# Team_Upsilon_Prj2_display_sch.net
KiCad netlist of a schematic drawn in Altium Designer
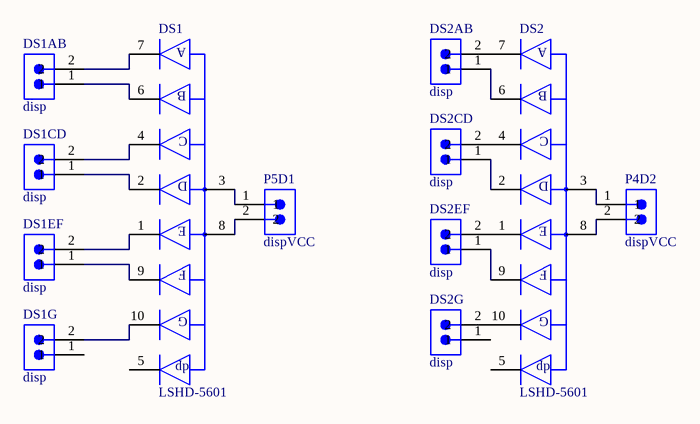
[diagram p0: Team_Upsilon_Prj2_display_sch.SchDoc]

(export (version "E")
  (design (tool "Eeschema 10.0.6"))
  (components
    (comp (ref "DS1")
      (value "LSHD-5601")
      (footprint "FP-LSHD-5601-MFG")
      (description "LED 7-SEG .56\" GREEN 565NM CA")
      (fields
        (field (name "MANUFACTURER") "Lite-On")
        (field (name "OCTOPART") "https://octopart.com/lshd-5601-lite-on-548440")
      )
      (libsource (lib "Altium Content Vault") (part "5a7bf9c30cf36056a9f9d601f88cd94"))
    )
    (comp (ref "DS1AB")
      (value "disp")
      (footprint "61300211121")
      (libsource (lib "Altium Content Vault") (part "Header_Male_1R_02P"))
    )
    (comp (ref "DS1CD")
      (value "disp")
      (footprint "61300211121")
      (libsource (lib "Altium Content Vault") (part "Header_Male_1R_02P"))
    )
    (comp (ref "DS1EF")
      (value "disp")
      (footprint "61300211121")
      (libsource (lib "Altium Content Vault") (part "Header_Male_1R_02P"))
    )
    (comp (ref "DS1G")
      (value "disp")
      (footprint "61300211121")
      (libsource (lib "Altium Content Vault") (part "Header_Male_1R_02P"))
    )
    (comp (ref "DS2")
      (value "LSHD-5601")
      (footprint "FP-LSHD-5601-MFG")
      (description "LED 7-SEG .56\" GREEN 565NM CA")
      (fields
        (field (name "MANUFACTURER") "Lite-On")
        (field (name "OCTOPART") "https://octopart.com/lshd-5601-lite-on-548440")
      )
      (libsource (lib "Altium Content Vault") (part "5a7bf9c30cf36056a9f9d601f88cd94"))
    )
    (comp (ref "DS2AB")
      (value "disp")
      (footprint "61300211121")
      (libsource (lib "Altium Content Vault") (part "Header_Male_1R_02P"))
    )
    (comp (ref "DS2CD")
      (value "disp")
      (footprint "61300211121")
      (libsource (lib "Altium Content Vault") (part "Header_Male_1R_02P"))
    )
    (comp (ref "DS2EF")
      (value "disp")
      (footprint "61300211121")
      (libsource (lib "Altium Content Vault") (part "Header_Male_1R_02P"))
    )
    (comp (ref "DS2G")
      (value "disp")
      (footprint "61300211121")
      (libsource (lib "Altium Content Vault") (part "Header_Male_1R_02P"))
    )
    (comp (ref "P4D2")
      (value "dispVCC")
      (footprint "61300211121")
      (libsource (lib "Altium Content Vault") (part "Header_Male_1R_02P"))
    )
    (comp (ref "P5D1")
      (value "dispVCC")
      (footprint "61300211121")
      (libsource (lib "Altium Content Vault") (part "Header_Male_1R_02P"))
    )
  )
  (nets
    (net (code "1") (name "Net-(DS1-CATHODE_A)") (class "Default")
      (node (ref "DS1") (pin "7") (pinfunction "CATHODE_A_7") (pintype "passive"))
      (node (ref "DS1AB") (pin "2") (pinfunction "2_2") (pintype "passive"))
    )
    (net (code "2") (name "Net-(DS1-CATHODE_B)") (class "Default")
      (node (ref "DS1") (pin "6") (pinfunction "CATHODE_B_6") (pintype "passive"))
      (node (ref "DS1AB") (pin "1") (pinfunction "1_1") (pintype "passive"))
    )
    (net (code "3") (name "Net-(DS1-CATHODE_C)") (class "Default")
      (node (ref "DS1") (pin "4") (pinfunction "CATHODE_C_4") (pintype "passive"))
      (node (ref "DS1CD") (pin "2") (pinfunction "2_2") (pintype "passive"))
    )
    (net (code "4") (name "Net-(DS1-CATHODE_D)") (class "Default")
      (node (ref "DS1") (pin "2") (pinfunction "CATHODE_D_2") (pintype "passive"))
      (node (ref "DS1CD") (pin "1") (pinfunction "1_1") (pintype "passive"))
    )
    (net (code "5") (name "Net-(DS1-CATHODE_E)") (class "Default")
      (node (ref "DS1") (pin "1") (pinfunction "CATHODE_E_1") (pintype "passive"))
      (node (ref "DS1EF") (pin "2") (pinfunction "2_2") (pintype "passive"))
    )
    (net (code "6") (name "Net-(DS1-CATHODE_F)") (class "Default")
      (node (ref "DS1") (pin "9") (pinfunction "CATHODE_F_9") (pintype "passive"))
      (node (ref "DS1EF") (pin "1") (pinfunction "1_1") (pintype "passive"))
    )
    (net (code "7") (name "Net-(DS1-CATHODE_G)") (class "Default")
      (node (ref "DS1") (pin "10") (pinfunction "CATHODE_G_10") (pintype "passive"))
      (node (ref "DS1G") (pin "2") (pinfunction "2_2") (pintype "passive"))
    )
    (net (code "8") (name "Net-(DS1-COMMON_ANODE-Pad3)") (class "Default")
      (node (ref "DS1") (pin "3") (pinfunction "COMMON_ANODE_3") (pintype "passive"))
      (node (ref "P5D1") (pin "1") (pinfunction "1_1") (pintype "passive"))
    )
    (net (code "9") (name "Net-(DS1-COMMON_ANODE-Pad8)") (class "Default")
      (node (ref "DS1") (pin "8") (pinfunction "COMMON_ANODE_8") (pintype "passive"))
      (node (ref "P5D1") (pin "2") (pinfunction "2_2") (pintype "passive"))
    )
    (net (code "10") (name "Net-(DS2-CATHODE_A)") (class "Default")
      (node (ref "DS2") (pin "7") (pinfunction "CATHODE_A_7") (pintype "passive"))
      (node (ref "DS2AB") (pin "2") (pinfunction "2_2") (pintype "passive"))
    )
    (net (code "11") (name "Net-(DS2-CATHODE_B)") (class "Default")
      (node (ref "DS2") (pin "6") (pinfunction "CATHODE_B_6") (pintype "passive"))
      (node (ref "DS2AB") (pin "1") (pinfunction "1_1") (pintype "passive"))
    )
    (net (code "12") (name "Net-(DS2-CATHODE_C)") (class "Default")
      (node (ref "DS2") (pin "4") (pinfunction "CATHODE_C_4") (pintype "passive"))
      (node (ref "DS2CD") (pin "2") (pinfunction "2_2") (pintype "passive"))
    )
    (net (code "13") (name "Net-(DS2-CATHODE_D)") (class "Default")
      (node (ref "DS2") (pin "2") (pinfunction "CATHODE_D_2") (pintype "passive"))
      (node (ref "DS2CD") (pin "1") (pinfunction "1_1") (pintype "passive"))
    )
    (net (code "14") (name "Net-(DS2-CATHODE_E)") (class "Default")
      (node (ref "DS2") (pin "1") (pinfunction "CATHODE_E_1") (pintype "passive"))
      (node (ref "DS2EF") (pin "2") (pinfunction "2_2") (pintype "passive"))
    )
    (net (code "15") (name "Net-(DS2-CATHODE_F)") (class "Default")
      (node (ref "DS2") (pin "9") (pinfunction "CATHODE_F_9") (pintype "passive"))
      (node (ref "DS2EF") (pin "1") (pinfunction "1_1") (pintype "passive"))
    )
    (net (code "16") (name "Net-(DS2-CATHODE_G)") (class "Default")
      (node (ref "DS2") (pin "10") (pinfunction "CATHODE_G_10") (pintype "passive"))
      (node (ref "DS2G") (pin "2") (pinfunction "2_2") (pintype "passive"))
    )
    (net (code "17") (name "Net-(DS2-COMMON_ANODE-Pad3)") (class "Default")
      (node (ref "DS2") (pin "3") (pinfunction "COMMON_ANODE_3") (pintype "passive"))
      (node (ref "P4D2") (pin "1") (pinfunction "1_1") (pintype "passive"))
    )
    (net (code "18") (name "Net-(DS2-COMMON_ANODE-Pad8)") (class "Default")
      (node (ref "DS2") (pin "8") (pinfunction "COMMON_ANODE_8") (pintype "passive"))
      (node (ref "P4D2") (pin "2") (pinfunction "2_2") (pintype "passive"))
    )
    (net (code "19") (name "unconnected-(DS1-CATHODE_DP-Pad5)") (class "Default")
      (node (ref "DS1") (pin "5") (pinfunction "CATHODE_DP_5") (pintype "passive"))
    )
    (net (code "20") (name "unconnected-(DS1G-Pad1)") (class "Default")
      (node (ref "DS1G") (pin "1") (pinfunction "1_1") (pintype "passive"))
    )
    (net (code "21") (name "unconnected-(DS2-CATHODE_DP-Pad5)") (class "Default")
      (node (ref "DS2") (pin "5") (pinfunction "CATHODE_DP_5") (pintype "passive"))
    )
    (net (code "22") (name "unconnected-(DS2G-Pad1)") (class "Default")
      (node (ref "DS2G") (pin "1") (pinfunction "1_1") (pintype "passive"))
    )
  )
)
